# Power_N2V5.net
KiCad netlist of a schematic drawn in Altium Designer
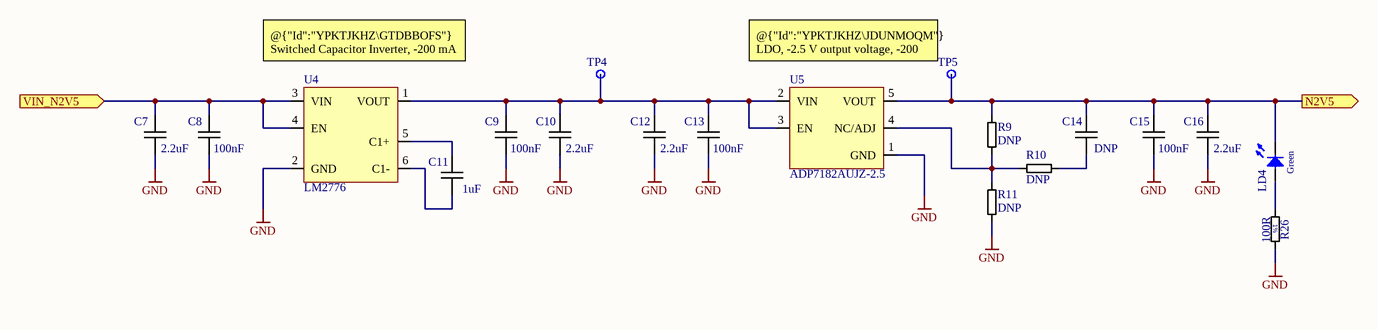
[diagram p0: Power_N2V5.SchDoc]

(export (version "E")
  (design (tool "Eeschema 10.0.6"))
  (components
    (comp (ref "C7")
      (value "2.2uF")
      (footprint "CAPC0603X90N")
      (description "Non-polarised capacitor")
      (fields (field (name "MANUFACTURER PART NUMBER") "GRM188Z71C225KE43D"))
      (libsource (lib "Capacitors") (part "Capacitor - non polarized"))
    )
    (comp (ref "C8")
      (value "100nF")
      (footprint "CAPC0603X90N")
      (description "Non-polarised capacitor")
      (fields (field (name "MANUFACTURER PART NUMBER") "VJ0603Y104KXJCW1BC"))
      (libsource (lib "Capacitors") (part "Capacitor - non polarized"))
    )
    (comp (ref "C9")
      (value "100nF")
      (footprint "CAPC0603X90N")
      (description "Non-polarised capacitor")
      (fields (field (name "MANUFACTURER PART NUMBER") "VJ0603Y104KXJCW1BC"))
      (libsource (lib "Capacitors") (part "Capacitor - non polarized"))
    )
    (comp (ref "C10")
      (value "2.2uF")
      (footprint "CAPC0603X90N")
      (description "Non-polarised capacitor")
      (fields (field (name "MANUFACTURER PART NUMBER") "GRM188Z71C225KE43D"))
      (libsource (lib "Capacitors") (part "Capacitor - non polarized"))
    )
    (comp (ref "C11")
      (value "1uF")
      (footprint "CAPC0603X90N")
      (description "Non-polarised capacitor")
      (fields (field (name "MANUFACTURER PART NUMBER") "CL10B105KO8NNNC"))
      (libsource (lib "Capacitors") (part "Capacitor - non polarized"))
    )
    (comp (ref "C12")
      (value "2.2uF")
      (footprint "CAPC0603X90N")
      (description "Non-polarised capacitor")
      (fields (field (name "MANUFACTURER PART NUMBER") "GRM188Z71C225KE43D"))
      (libsource (lib "Capacitors") (part "Capacitor - non polarized"))
    )
    (comp (ref "C13")
      (value "100nF")
      (footprint "CAPC0603X90N")
      (description "Non-polarised capacitor")
      (fields (field (name "MANUFACTURER PART NUMBER") "VJ0603Y104KXJCW1BC"))
      (libsource (lib "Capacitors") (part "Capacitor - non polarized"))
    )
    (comp (ref "C14")
      (value "DNP")
      (footprint "CAPC0603X90N")
      (description "Non-polarised capacitor")
      (fields (field (name "MANUFACTURER PART NUMBER") "UNDEFINED"))
      (libsource (lib "Capacitors") (part "Capacitor - non polarized"))
    )
    (comp (ref "C15")
      (value "100nF")
      (footprint "CAPC0603X90N")
      (description "Non-polarised capacitor")
      (fields (field (name "MANUFACTURER PART NUMBER") "VJ0603Y104KXJCW1BC"))
      (libsource (lib "Capacitors") (part "Capacitor - non polarized"))
    )
    (comp (ref "C16")
      (value "2.2uF")
      (footprint "CAPC0603X90N")
      (description "Non-polarised capacitor")
      (fields (field (name "MANUFACTURER PART NUMBER") "GRM188Z71C225KE43D"))
      (libsource (lib "Capacitors") (part "Capacitor - non polarized"))
    )
    (comp (ref "LD4")
      (value "Green")
      (footprint "LED_0603X60N")
      (description "SMD mono-color Chip LED, Green, 0603")
      (fields (field (name "MANUFACTURER PART NUMBER") "HSME-C191"))
      (libsource (lib "ICs_and_Semiconductors") (part "LED 1C 2A"))
    )
    (comp (ref "R9")
      (value "DNP")
      (footprint "RESC0402X40N")
      (description "General Purpose Thick Film Chip Resistor")
      (fields (field (name "VOLTAGE") "50V"))
      (libsource (lib "Resistors") (part "Resistor - Generic"))
    )
    (comp (ref "R10")
      (value "DNP")
      (footprint "RESC0402X40N")
      (description "General Purpose Thick Film Chip Resistor")
      (fields (field (name "VOLTAGE") "50V"))
      (libsource (lib "Resistors") (part "Resistor - Generic"))
    )
    (comp (ref "R11")
      (value "DNP")
      (footprint "RESC0402X40N")
      (description "General Purpose Thick Film Chip Resistor")
      (fields (field (name "VOLTAGE") "50V"))
      (libsource (lib "Resistors") (part "Resistor - Generic"))
    )
    (comp (ref "R26")
      (value "100R")
      (footprint "RESC0603X60N")
      (description "General Purpose Thick Film Chip Resistor")
      (fields (field (name "MANUFACTURER PART NUMBER") "0603SAF1000T5E") (field (name "TOLERANCE") "1%"))
      (libsource (lib "Resistors") (part "Resistor - 1%"))
    )
    (comp (ref "TP4")
      (value "TestPoint")
      (footprint "TESTPOINT_SMD_C1P27MM")
      (description "1.27mm diameter SMD Test Point Area")
      (libsource (lib "Mechanical_and_PCB_Features") (part "Test Point"))
    )
    (comp (ref "TP5")
      (value "TestPoint")
      (footprint "TESTPOINT_SMD_C1P27MM")
      (description "1.27mm diameter SMD Test Point Area")
      (libsource (lib "Mechanical_and_PCB_Features") (part "Test Point"))
    )
    (comp (ref "U4")
      (value "LM2776")
      (footprint "SOT23-6")
      (description "Switched Capacitor Inverter, Input Voltage: 2.7 V to 5.5 V, 200-mA Output Current")
      (fields (field (name "MANUFACTURER PART NUMBER") "LM2776DBV(_)"))
      (libsource (lib "ICs_and_Semiconductors") (part "LM2776"))
    )
    (comp (ref "U5")
      (value "ADP7182AUJZ-2.5")
      (footprint "SOT23-5")
      (description "LDO Voltage Regulators -30V, 200mA, low noise, Linear Reg, 2.5V")
      (libsource (lib "ICs_and_Semiconductors") (part "ADP7182AUJZ"))
    )
  )
  (nets
    (net (code "1") (name "/N2V5") (class "Default")
      (node (ref "C14") (pin "1") (pinfunction "1_1") (pintype "passive"))
      (node (ref "C15") (pin "1") (pinfunction "1_1") (pintype "passive"))
      (node (ref "C16") (pin "1") (pinfunction "1_1") (pintype "passive"))
      (node (ref "LD4") (pin "1") (pinfunction "C_1") (pintype "passive"))
      (node (ref "R9") (pin "2") (pinfunction "2_2") (pintype "passive"))
      (node (ref "TP5") (pin "1") (pinfunction "1_1") (pintype "passive"))
      (node (ref "U5") (pin "5") (pinfunction "VOUT_5") (pintype "passive"))
    )
    (net (code "2") (name "/VIN_N2V5") (class "Default")
      (node (ref "C7") (pin "1") (pinfunction "1_1") (pintype "passive"))
      (node (ref "C8") (pin "1") (pinfunction "1_1") (pintype "passive"))
      (node (ref "U4") (pin "3") (pinfunction "VIN_3") (pintype "passive"))
      (node (ref "U4") (pin "4") (pinfunction "EN_4") (pintype "passive"))
    )
    (net (code "3") (name "GND") (class "Default")
      (node (ref "C10") (pin "2") (pinfunction "2_2") (pintype "passive"))
      (node (ref "C12") (pin "2") (pinfunction "2_2") (pintype "passive"))
      (node (ref "C13") (pin "2") (pinfunction "2_2") (pintype "passive"))
      (node (ref "C15") (pin "2") (pinfunction "2_2") (pintype "passive"))
      (node (ref "C16") (pin "2") (pinfunction "2_2") (pintype "passive"))
      (node (ref "C7") (pin "2") (pinfunction "2_2") (pintype "passive"))
      (node (ref "C8") (pin "2") (pinfunction "2_2") (pintype "passive"))
      (node (ref "C9") (pin "2") (pinfunction "2_2") (pintype "passive"))
      (node (ref "R11") (pin "1") (pinfunction "1_1") (pintype "passive"))
      (node (ref "R26") (pin "2") (pinfunction "2_2") (pintype "passive"))
      (node (ref "U4") (pin "2") (pinfunction "GND_2") (pintype "power_in"))
      (node (ref "U5") (pin "1") (pinfunction "GND_1") (pintype "power_in"))
    )
    (net (code "4") (name "Net-(C14-Pad2)") (class "Default")
      (node (ref "C14") (pin "2") (pinfunction "2_2") (pintype "passive"))
      (node (ref "R10") (pin "1") (pinfunction "1_1") (pintype "passive"))
    )
    (net (code "5") (name "Net-(LD4-A)") (class "Default")
      (node (ref "LD4") (pin "2") (pinfunction "A_2") (pintype "passive"))
      (node (ref "R26") (pin "1") (pinfunction "1_1") (pintype "passive"))
    )
    (net (code "6") (name "Net-(U4-C1+)") (class "Default")
      (node (ref "C11") (pin "1") (pinfunction "1_1") (pintype "passive"))
      (node (ref "U4") (pin "5") (pinfunction "C1+_5") (pintype "passive"))
    )
    (net (code "7") (name "Net-(U4-C1-)") (class "Default")
      (node (ref "C11") (pin "2") (pinfunction "2_2") (pintype "passive"))
      (node (ref "U4") (pin "6") (pinfunction "C1-_6") (pintype "passive"))
    )
    (net (code "8") (name "Net-(U4-VOUT)") (class "Default")
      (node (ref "C10") (pin "1") (pinfunction "1_1") (pintype "passive"))
      (node (ref "C12") (pin "1") (pinfunction "1_1") (pintype "passive"))
      (node (ref "C13") (pin "1") (pinfunction "1_1") (pintype "passive"))
      (node (ref "C9") (pin "1") (pinfunction "1_1") (pintype "passive"))
      (node (ref "TP4") (pin "1") (pinfunction "1_1") (pintype "passive"))
      (node (ref "U4") (pin "1") (pinfunction "VOUT_1") (pintype "passive"))
      (node (ref "U5") (pin "2") (pinfunction "VIN_2") (pintype "passive"))
      (node (ref "U5") (pin "3") (pinfunction "EN_3") (pintype "passive"))
    )
    (net (code "9") (name "Net-(U5-NC{slash}ADJ)") (class "Default")
      (node (ref "R10") (pin "2") (pinfunction "2_2") (pintype "passive"))
      (node (ref "R11") (pin "2") (pinfunction "2_2") (pintype "passive"))
      (node (ref "R9") (pin "1") (pinfunction "1_1") (pintype "passive"))
      (node (ref "U5") (pin "4") (pinfunction "NC/ADJ_4") (pintype "passive"))
    )
  )
)
